# LAB-01.net
KiCad netlist of a schematic drawn in Altium Designer
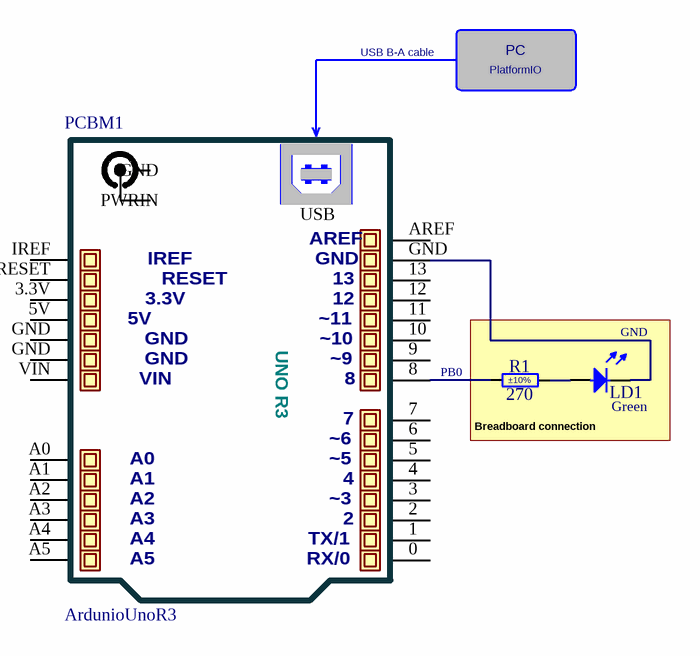
[diagram p0: LAB-01.SchDoc]

(export (version "E")
  (design (tool "Eeschema 10.0.6"))
  (components
    (comp (ref "LD1")
      (value "Green")
      (footprint "LED_DIALIGHT_561-2201-050F")
      (description "LED Green 1C 2A")
      (fields
        (field (name "PART NUMBER") "LED_DIALIGHT_561-2201-050F")
        (field (name "MANUFACTURER") "DIALIGHT")
        (field (name "AUTHOR") "CERN DEM JLC")
      )
      (libsource (lib "ICs And Semiconductors") (part "LED Green 1C 2A"))
    )
    (comp (ref "PCBM1")
      (value "ArdunioUnoR3")
      (description "ArdunioUnoR3 Universal SCH Symbol \r\n(C) 230232")
      (libsource (lib "ArduinoUnoR3") (part "ArdunioUnoR3"))
    )
    (comp (ref "R1")
      (value "270")
      (footprint "RESC3216X65N")
      (description "Resistor - 0.1%")
      (fields
        (field (name "TOLERANCE") "±10%")
        (field (name "PART NUMBER") "R1206_270R_0.1%_0.25W_25PPM")
        (field (name "POWER") "0.25W")
        (field (name "AUTHOR") "CERN DEM JLC")
      )
      (libsource (lib "Resistors") (part "Resistor - 0.1%"))
    )
  )
  (nets
    (net (code "1") (name "Net-(LD1-A)") (class "Default")
      (node (ref "LD1") (pin "2") (pinfunction "A_2") (pintype "passive"))
      (node (ref "R1") (pin "2") (pinfunction "2_2") (pintype "passive"))
    )
    (net (code "2") (name "Net-(LD1-C)") (class "Default")
      (node (ref "LD1") (pin "1") (pinfunction "C_1") (pintype "passive"))
      (node (ref "PCBM1") (pin "GND") (pinfunction "GND_GND") (pintype "passive"))
    )
    (net (code "3") (name "Net-(PCBM1-Pad8)") (class "Default")
      (node (ref "PCBM1") (pin "8") (pinfunction "8_8") (pintype "passive"))
      (node (ref "R1") (pin "1") (pinfunction "1_1") (pintype "passive"))
    )
    (net (code "4") (name "unconnected-(PCBM1-Pad0)") (class "Default")
      (node (ref "PCBM1") (pin "0") (pinfunction "0_0") (pintype "passive"))
    )
    (net (code "5") (name "unconnected-(PCBM1-Pad1)") (class "Default")
      (node (ref "PCBM1") (pin "1") (pinfunction "1_1") (pintype "passive"))
    )
    (net (code "6") (name "unconnected-(PCBM1-Pad2)") (class "Default")
      (node (ref "PCBM1") (pin "2") (pinfunction "2_2") (pintype "passive"))
    )
    (net (code "7") (name "unconnected-(PCBM1-Pad3)") (class "Default")
      (node (ref "PCBM1") (pin "3") (pinfunction "3_3") (pintype "passive"))
    )
    (net (code "8") (name "unconnected-(PCBM1-Pad3.3V)") (class "Default")
      (node (ref "PCBM1") (pin "3.3V") (pinfunction "3.3V_3.3V") (pintype "passive"))
    )
    (net (code "9") (name "unconnected-(PCBM1-Pad4)") (class "Default")
      (node (ref "PCBM1") (pin "4") (pinfunction "4_4") (pintype "passive"))
    )
    (net (code "10") (name "unconnected-(PCBM1-Pad5)") (class "Default")
      (node (ref "PCBM1") (pin "5") (pinfunction "5_5") (pintype "passive"))
    )
    (net (code "11") (name "unconnected-(PCBM1-Pad5V)") (class "Default")
      (node (ref "PCBM1") (pin "5V") (pinfunction "5V_5V") (pintype "passive"))
    )
    (net (code "12") (name "unconnected-(PCBM1-Pad6)") (class "Default")
      (node (ref "PCBM1") (pin "6") (pinfunction "6_6") (pintype "passive"))
    )
    (net (code "13") (name "unconnected-(PCBM1-Pad7)") (class "Default")
      (node (ref "PCBM1") (pin "7") (pinfunction "7_7") (pintype "passive"))
    )
    (net (code "14") (name "unconnected-(PCBM1-Pad9)") (class "Default")
      (node (ref "PCBM1") (pin "9") (pinfunction "9_9") (pintype "passive"))
    )
    (net (code "15") (name "unconnected-(PCBM1-Pad10)") (class "Default")
      (node (ref "PCBM1") (pin "10") (pinfunction "10_10") (pintype "passive"))
    )
    (net (code "16") (name "unconnected-(PCBM1-Pad11)") (class "Default")
      (node (ref "PCBM1") (pin "11") (pinfunction "11_11") (pintype "passive"))
    )
    (net (code "17") (name "unconnected-(PCBM1-Pad12)") (class "Default")
      (node (ref "PCBM1") (pin "12") (pinfunction "12_12") (pintype "passive"))
    )
    (net (code "18") (name "unconnected-(PCBM1-Pad13)") (class "Default")
      (node (ref "PCBM1") (pin "13") (pinfunction "13_13") (pintype "passive"))
    )
    (net (code "19") (name "unconnected-(PCBM1-PadA0)") (class "Default")
      (node (ref "PCBM1") (pin "A0") (pinfunction "A0_A0") (pintype "passive"))
    )
    (net (code "20") (name "unconnected-(PCBM1-PadA1)") (class "Default")
      (node (ref "PCBM1") (pin "A1") (pinfunction "A1_A1") (pintype "passive"))
    )
    (net (code "21") (name "unconnected-(PCBM1-PadA2)") (class "Default")
      (node (ref "PCBM1") (pin "A2") (pinfunction "A2_A2") (pintype "passive"))
    )
    (net (code "22") (name "unconnected-(PCBM1-PadA3)") (class "Default")
      (node (ref "PCBM1") (pin "A3") (pinfunction "A3_A3") (pintype "passive"))
    )
    (net (code "23") (name "unconnected-(PCBM1-PadA4)") (class "Default")
      (node (ref "PCBM1") (pin "A4") (pinfunction "A4_A4") (pintype "passive"))
    )
    (net (code "24") (name "unconnected-(PCBM1-PadA5)") (class "Default")
      (node (ref "PCBM1") (pin "A5") (pinfunction "A5_A5") (pintype "passive"))
    )
    (net (code "25") (name "unconnected-(PCBM1-PadAREF)") (class "Default")
      (node (ref "PCBM1") (pin "AREF") (pinfunction "AREF_AREF") (pintype "passive"))
    )
    (net (code "26") (name "unconnected-(PCBM1-PadGND)") (class "Default")
      (node (ref "PCBM1") (pin "GND") (pinfunction "GND_GND") (pintype "passive"))
    )
    (net (code "27") (name "unconnected-(PCBM1-PadGND)_1") (class "Default")
      (node (ref "PCBM1") (pin "GND") (pinfunction "GND_GND") (pintype "passive"))
    )
    (net (code "28") (name "unconnected-(PCBM1-PadIREF)") (class "Default")
      (node (ref "PCBM1") (pin "IREF") (pinfunction "IREF_IREF") (pintype "passive"))
    )
    (net (code "29") (name "unconnected-(PCBM1-PadRESET)") (class "Default")
      (node (ref "PCBM1") (pin "RESET") (pinfunction "RESET_RESET") (pintype "passive"))
    )
    (net (code "30") (name "unconnected-(PCBM1-PadVIN)") (class "Default")
      (node (ref "PCBM1") (pin "VIN") (pinfunction "VIN_VIN") (pintype "passive"))
    )
  )
)
